# RowSingle.net
KiCad netlist of a schematic drawn in Altium Designer
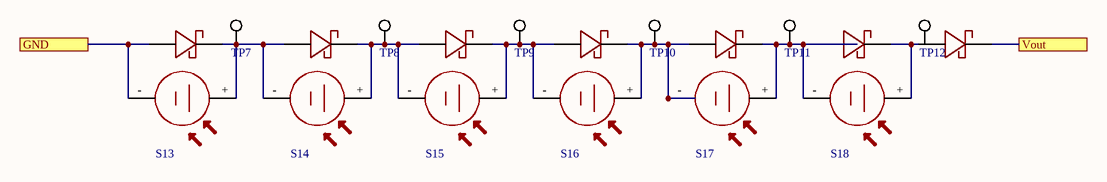
[diagram p0: RowSingle.SchDoc]

(export (version "E")
  (design (tool "Eeschema 10.0.6"))
  (components
    (comp (ref "D8")
      (value "SCHOTTKY_DIODE_B120-FDICT-NDSCHOTTKY_DIODE_B120-FDICT-ND")
      (footprint "SB_DIODE")
      (fields (field (name "LIBRARYNAME") "Solar_Fadi"))
      (libsource (lib "SchLib") (part "SCHOTTKY_DIODE_B120-FDICT-NDSCHOTTKY_DIODE_B120-FDICT-ND"))
    )
    (comp (ref "D9")
      (value "SCHOTTKY_DIODE_B120-FDICT-NDSCHOTTKY_DIODE_B120-FDICT-ND")
      (footprint "SB_DIODE")
      (fields (field (name "LIBRARYNAME") "Solar_Fadi"))
      (libsource (lib "SchLib") (part "SCHOTTKY_DIODE_B120-FDICT-NDSCHOTTKY_DIODE_B120-FDICT-ND"))
    )
    (comp (ref "D10")
      (value "SCHOTTKY_DIODE_B120-FDICT-NDSCHOTTKY_DIODE_B120-FDICT-ND")
      (footprint "SB_DIODE")
      (fields (field (name "LIBRARYNAME") "Solar_Fadi"))
      (libsource (lib "SchLib") (part "SCHOTTKY_DIODE_B120-FDICT-NDSCHOTTKY_DIODE_B120-FDICT-ND"))
    )
    (comp (ref "D11")
      (value "SCHOTTKY_DIODE_B120-FDICT-NDSCHOTTKY_DIODE_B120-FDICT-ND")
      (footprint "SB_DIODE")
      (fields (field (name "LIBRARYNAME") "Solar_Fadi"))
      (libsource (lib "SchLib") (part "SCHOTTKY_DIODE_B120-FDICT-NDSCHOTTKY_DIODE_B120-FDICT-ND"))
    )
    (comp (ref "D12")
      (value "SCHOTTKY_DIODE_B120-FDICT-NDSCHOTTKY_DIODE_B120-FDICT-ND")
      (footprint "SB_DIODE")
      (fields (field (name "LIBRARYNAME") "Solar_Fadi"))
      (libsource (lib "SchLib") (part "SCHOTTKY_DIODE_B120-FDICT-NDSCHOTTKY_DIODE_B120-FDICT-ND"))
    )
    (comp (ref "D13")
      (value "SCHOTTKY_DIODE_B120-FDICT-NDSCHOTTKY_DIODE_B120-FDICT-ND")
      (footprint "SB_DIODE")
      (fields (field (name "LIBRARYNAME") "Solar_Fadi"))
      (libsource (lib "") (part "SCHOTTKY_DIODE_B120-FDICT-NDSCHOTTKY_DIODE_B120-FDICT-ND_1"))
    )
    (comp (ref "D14")
      (value "SCHOTTKY_DIODE_B120-FDICT-NDSCHOTTKY_DIODE_B120-FDICT-ND")
      (footprint "SB_DIODE")
      (fields (field (name "LIBRARYNAME") "Solar_Fadi"))
      (libsource (lib "SchLib") (part "SCHOTTKY_DIODE_B120-FDICT-NDSCHOTTKY_DIODE_B120-FDICT-ND"))
    )
    (comp (ref "S13")
      (value "SOLAR_CELL")
      (footprint "SOLAR_CELL")
      (libsource (lib "SchLib") (part "SOLAR_CELL"))
    )
    (comp (ref "S14")
      (value "SOLAR_CELL")
      (footprint "SOLAR_CELL")
      (libsource (lib "SchLib") (part "SOLAR_CELL"))
    )
    (comp (ref "S15")
      (value "SOLAR_CELL")
      (footprint "SOLAR_CELL")
      (libsource (lib "SchLib") (part "SOLAR_CELL"))
    )
    (comp (ref "S16")
      (value "SOLAR_CELL")
      (footprint "SOLAR_CELL")
      (libsource (lib "SchLib") (part "SOLAR_CELL"))
    )
    (comp (ref "S17")
      (value "SOLAR_CELL")
      (footprint "SOLAR_CELL")
      (libsource (lib "SchLib") (part "SOLAR_CELL"))
    )
    (comp (ref "S18")
      (value "SOLAR_CELL")
      (footprint "SOLAR_CELL")
      (libsource (lib "SchLib") (part "SOLAR_CELL"))
    )
    (comp (ref "TP7")
      (value "TEST_POINT")
      (footprint "TEST_POINT")
      (libsource (lib "SchLib") (part "TEST_POINT"))
    )
    (comp (ref "TP8")
      (value "TEST_POINT")
      (footprint "TEST_POINT")
      (libsource (lib "SchLib") (part "TEST_POINT"))
    )
    (comp (ref "TP9")
      (value "TEST_POINT")
      (footprint "TEST_POINT")
      (libsource (lib "SchLib") (part "TEST_POINT"))
    )
    (comp (ref "TP10")
      (value "TEST_POINT")
      (footprint "TEST_POINT")
      (libsource (lib "SchLib") (part "TEST_POINT"))
    )
    (comp (ref "TP11")
      (value "TEST_POINT")
      (footprint "TEST_POINT")
      (libsource (lib "SchLib") (part "TEST_POINT"))
    )
    (comp (ref "TP12")
      (value "TEST_POINT")
      (footprint "TEST_POINT")
      (libsource (lib "SchLib") (part "TEST_POINT"))
    )
  )
  (nets
    (net (code "1") (name "/GND") (class "Default")
      (node (ref "D8") (pin "POS") (pinfunction "POS_POS") (pintype "passive"))
      (node (ref "S13") (pin "-") (pinfunction "-_-") (pintype "passive"))
    )
    (net (code "2") (name "/Vout") (class "Default")
      (node (ref "D14") (pin "NEG") (pinfunction "NEG_NEG") (pintype "passive"))
    )
    (net (code "3") (name "Net-(D8-PadNEG)") (class "Default")
      (node (ref "D8") (pin "NEG") (pinfunction "NEG_NEG") (pintype "passive"))
      (node (ref "D9") (pin "POS") (pinfunction "POS_POS") (pintype "passive"))
      (node (ref "S13") (pin "+") (pinfunction "+_+") (pintype "passive"))
      (node (ref "S14") (pin "-") (pinfunction "-_-") (pintype "passive"))
      (node (ref "TP7") (pin "38") (pinfunction "38_38") (pintype "passive"))
    )
    (net (code "4") (name "Net-(D10-PadNEG)") (class "Default")
      (node (ref "D10") (pin "NEG") (pinfunction "NEG_NEG") (pintype "passive"))
      (node (ref "D11") (pin "POS") (pinfunction "POS_POS") (pintype "passive"))
      (node (ref "S15") (pin "+") (pinfunction "+_+") (pintype "passive"))
      (node (ref "S16") (pin "-") (pinfunction "-_-") (pintype "passive"))
      (node (ref "TP9") (pin "38") (pinfunction "38_38") (pintype "passive"))
    )
    (net (code "5") (name "Net-(D10-PadPOS)") (class "Default")
      (node (ref "D10") (pin "POS") (pinfunction "POS_POS") (pintype "passive"))
      (node (ref "D9") (pin "NEG") (pinfunction "NEG_NEG") (pintype "passive"))
      (node (ref "S14") (pin "+") (pinfunction "+_+") (pintype "passive"))
      (node (ref "S15") (pin "-") (pinfunction "-_-") (pintype "passive"))
      (node (ref "TP8") (pin "38") (pinfunction "38_38") (pintype "passive"))
    )
    (net (code "6") (name "Net-(D11-PadNEG)") (class "Default")
      (node (ref "D11") (pin "NEG") (pinfunction "NEG_NEG") (pintype "passive"))
      (node (ref "D12") (pin "POS") (pinfunction "POS_POS") (pintype "passive"))
      (node (ref "S16") (pin "+") (pinfunction "+_+") (pintype "passive"))
      (node (ref "S17") (pin "-") (pinfunction "-_-") (pintype "passive"))
      (node (ref "TP10") (pin "38") (pinfunction "38_38") (pintype "passive"))
    )
    (net (code "7") (name "Net-(D12-PadNEG)") (class "Default")
      (node (ref "D12") (pin "NEG") (pinfunction "NEG_NEG") (pintype "passive"))
      (node (ref "S17") (pin "+") (pinfunction "+_+") (pintype "passive"))
      (node (ref "S18") (pin "-") (pinfunction "-_-") (pintype "passive"))
      (node (ref "TP11") (pin "38") (pinfunction "38_38") (pintype "passive"))
    )
    (net (code "8") (name "Net-(D13-PadNEG)") (class "Default")
      (node (ref "D13") (pin "NEG") (pinfunction "NEG_NEG") (pintype "passive"))
      (node (ref "D14") (pin "POS") (pinfunction "POS_POS") (pintype "passive"))
      (node (ref "S18") (pin "+") (pinfunction "+_+") (pintype "passive"))
    )
    (net (code "9") (name "unconnected-(TP12-Pad38)") (class "Default")
      (node (ref "TP12") (pin "38") (pinfunction "38_38") (pintype "passive"))
    )
  )
)
